# Gateway.net
KiCad netlist of a schematic drawn in Altium Designer
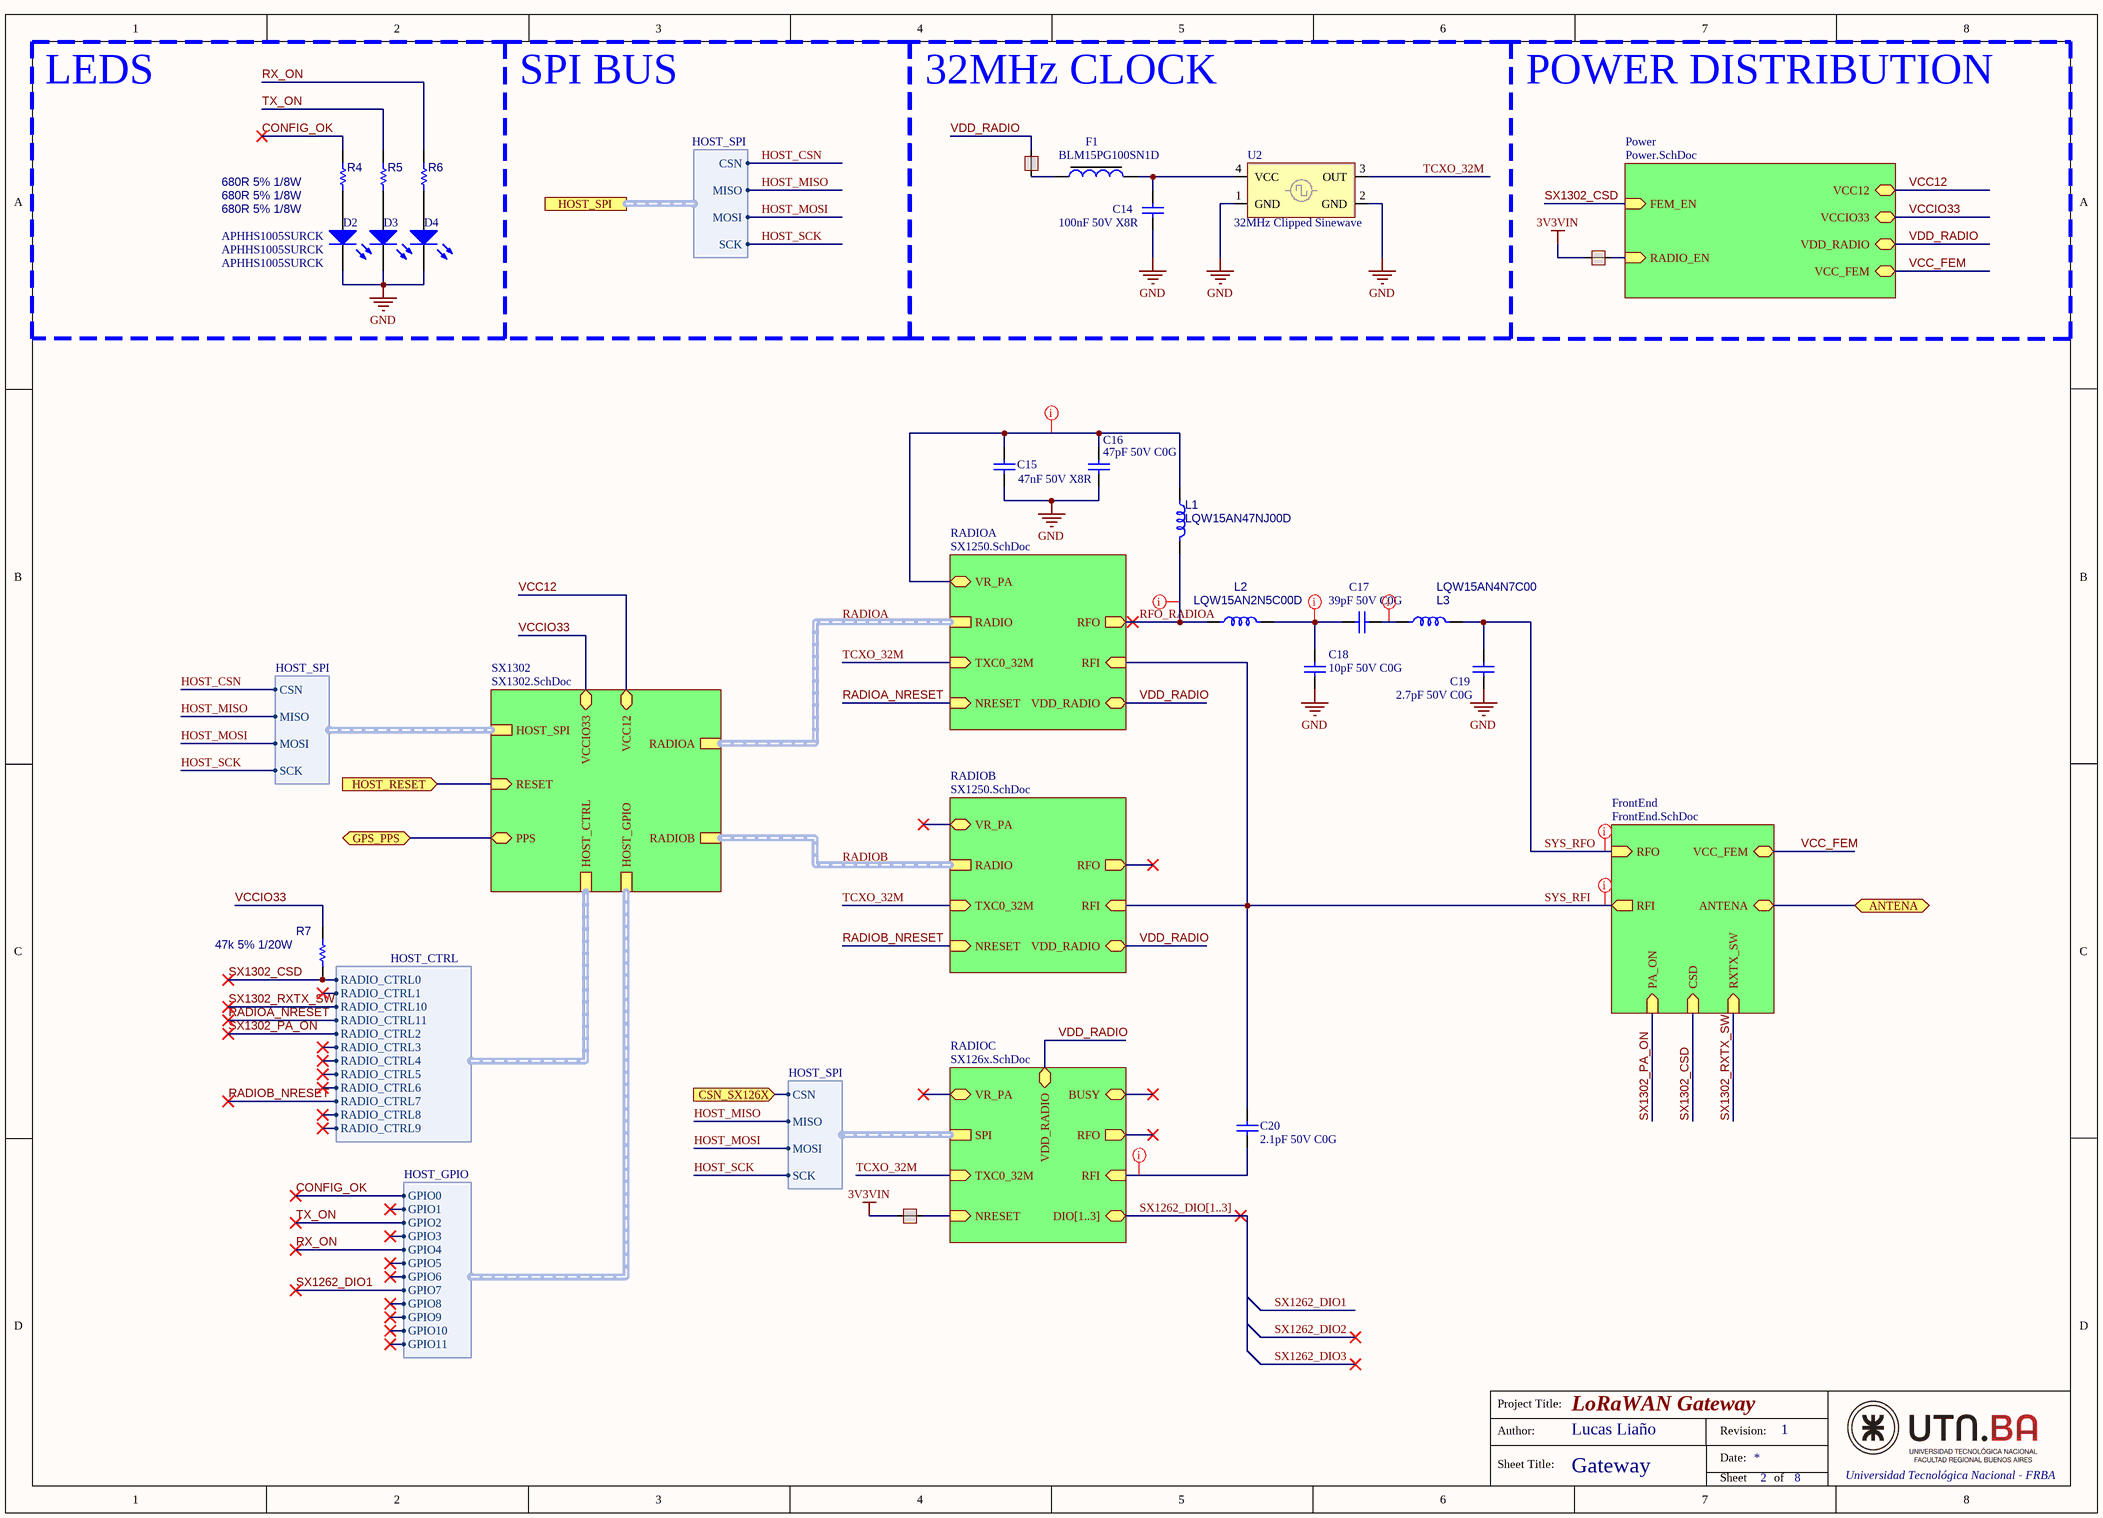
[diagram p0: Gateway.SchDoc]

(export (version "E")
  (design (tool "Eeschema 10.0.6"))
  (components
    (comp (ref "C14")
      (value "100nF 50V X8R")
      (footprint "C_0603")
      (description "Capacitor")
      (fields (field (name "MPN") "GCM188R91H102KA37D") (field (name "MANUFACTURER") "Murata Electronics"))
      (libsource (lib "lorawan_gateway") (part "Cap"))
    )
    (comp (ref "C15")
      (value "47nF 50V X8R")
      (footprint "C_0603")
      (description "Capacitor")
      (fields (field (name "MPN") "GCM188R91H472KA37D") (field (name "MANUFACTURER") "Murata Electronics"))
      (libsource (lib "lorawan_gateway") (part "Cap"))
    )
    (comp (ref "C16")
      (value "47pF 50V C0G")
      (footprint "C_0603")
      (description "Capacitor")
      (fields (field (name "MPN") "0603J0500470GAT") (field (name "MANUFACTURER") "Knowless Syfer"))
      (libsource (lib "lorawan_gateway") (part "Cap"))
    )
    (comp (ref "C17")
      (value "39pF 50V C0G")
      (footprint "C_0603")
      (description "Capacitor")
      (fields (field (name "MPN") "06035A390FAT2A") (field (name "MANUFACTURER") "Kyocera AVX"))
      (libsource (lib "lorawan_gateway") (part "Cap"))
    )
    (comp (ref "C18")
      (value "10pF 50V C0G")
      (footprint "C_0603")
      (description "Capacitor")
      (fields (field (name "MPN") "GRM0335C1H100FA01D") (field (name "MANUFACTURER") "Murata Electronics"))
      (libsource (lib "lorawan_gateway") (part "Cap"))
    )
    (comp (ref "C19")
      (value "2.7pF 50V C0G")
      (footprint "C_0603")
      (description "Capacitor")
      (fields (field (name "MPN") "GRM0335C1H2R7WA01D") (field (name "MANUFACTURER") "Murata Electronics"))
      (libsource (lib "lorawan_gateway") (part "Cap"))
    )
    (comp (ref "C20")
      (value "2.1pF 50V C0G")
      (footprint "C_0603")
      (description "Capacitor")
      (fields (field (name "MPN") "ML03512R1BAT2A") (field (name "MANUFACTURER") "Kyocera AVX"))
      (libsource (lib "lorawan_gateway") (part "Cap"))
    )
    (comp (ref "D2")
      (value "APHHS1005SURCK")
      (footprint "D_0402")
      (description "LED")
      (fields (field (name "MANUFACTURER") "kingbright"))
      (libsource (lib "lorawan_gateway") (part "LED"))
    )
    (comp (ref "D3")
      (value "APHHS1005SURCK")
      (footprint "D_0402")
      (description "LED")
      (fields (field (name "MANUFACTURER") "kingbright"))
      (libsource (lib "lorawan_gateway") (part "LED"))
    )
    (comp (ref "D4")
      (value "APHHS1005SURCK")
      (footprint "D_0402")
      (description "LED")
      (fields (field (name "MANUFACTURER") "kingbright"))
      (libsource (lib "lorawan_gateway") (part "LED"))
    )
    (comp (ref "F1")
      (value "BLM15PG100SN1D")
      (footprint "L_0402")
      (description "Ferrite bead 10 ohm 1A")
      (fields (field (name "MANUFACTURER") "Murata Electronics"))
      (libsource (lib "lorawan_gateway") (part "Ferrite beads"))
    )
    (comp (ref "L1")
      (value "LQW15AN47NJ00D")
      (footprint "L_0402")
      (description "Inductor")
      (libsource (lib "lorawan_gateway") (part "IND"))
    )
    (comp (ref "L2")
      (value "LQW15AN2N5C00D")
      (footprint "L_0402")
      (description "Inductor")
      (libsource (lib "lorawan_gateway") (part "IND"))
    )
    (comp (ref "L3")
      (value "LQW15AN4N7C00")
      (footprint "L_0402")
      (description "Inductor")
      (libsource (lib "lorawan_gateway") (part "IND"))
    )
    (comp (ref "NT1")
      (value "NT")
      (footprint "NTIE12")
      (description "NET_TIE")
      (libsource (lib "lorawan_gateway") (part "NTIE"))
    )
    (comp (ref "NT13")
      (value "NT")
      (footprint "NTIE12")
      (description "NET_TIE")
      (libsource (lib "") (part "NTIE_1"))
    )
    (comp (ref "NT15")
      (value "NT")
      (footprint "NTIE12")
      (description "NET_TIE")
      (libsource (lib "lorawan_gateway") (part "NTIE"))
    )
    (comp (ref "R4")
      (value "680R 5% 1/8W")
      (footprint "0603[1608]")
      (description "Resistor")
      (fields
        (field (name "MANUFACTURER") "Panasonic Electronic Components")
        (field (name "MPN") "ERJ-H3GJ681V")
      )
      (libsource (lib "lorawan_gateway") (part "Res"))
    )
    (comp (ref "R5")
      (value "680R 5% 1/8W")
      (footprint "0603[1608]")
      (description "Resistor")
      (fields
        (field (name "MANUFACTURER") "Panasonic Electronic Components")
        (field (name "MPN") "ERJ-H3GJ681V")
      )
      (libsource (lib "lorawan_gateway") (part "Res"))
    )
    (comp (ref "R6")
      (value "680R 5% 1/8W")
      (footprint "0603[1608]")
      (description "Resistor")
      (fields
        (field (name "MANUFACTURER") "Panasonic Electronic Components")
        (field (name "MPN") "ERJ-H3GJ681V")
      )
      (libsource (lib "lorawan_gateway") (part "Res"))
    )
    (comp (ref "R7")
      (value "47k 5% 1/20W")
      (footprint "0603[1608]")
      (description "Resistor")
      (fields (field (name "MANUFACTURER") "Vishay") (field (name "MPN") "M55342K11B47K0MT1V"))
      (libsource (lib "lorawan_gateway") (part "Res"))
    )
    (comp (ref "U2")
      (value "32MHz Clipped Sinewave")
      (footprint "TCXO 2.0x1.6mm")
      (description "32MHz TCXO - Clipped Sinewave Output")
      (fields (field (name "MANUFACTURER") "NDK America") (field (name "MPN") "NT2016SA 32MHz END4263A"))
      (libsource (lib "lorawan_gateway") (part "TCXO"))
    )
  )
  (nets
    (net (code "8") (name "/CONFIG_OK") (class "Default")
      (node (ref "R4") (pin "2") (pinfunction "2_2") (pintype "passive+no_connect"))
    )
    (net (code "16") (name "/NRESET") (class "Default")
      (node (ref "NT1") (pin "2") (pinfunction "2_2") (pintype "passive"))
    )
    (net (code "19") (name "/RADIO_EN") (class "Default")
      (node (ref "NT15") (pin "2") (pinfunction "2_2") (pintype "passive"))
    )
    (net (code "20") (name "/RFI") (class "Default")
      (node (ref "C20") (pin "1") (pinfunction "1_1") (pintype "passive"))
    )
    (net (code "23") (name "/RFO_RADIOA") (class "Default")
      (node (ref "L1") (pin "2") (pinfunction "2_2") (pintype "passive"))
      (node (ref "L2") (pin "1") (pinfunction "1_1") (pintype "passive"))
    )
    (net (code "24") (name "/RX_ON") (class "Default")
      (node (ref "R6") (pin "2") (pinfunction "2_2") (pintype "passive"))
    )
    (net (code "29") (name "/SX1302_CSD") (class "Default")
      (node (ref "R7") (pin "1") (pinfunction "1_1") (pintype "passive+no_connect"))
    )
    (net (code "32") (name "/SYS_RFI") (class "Default")
      (node (ref "C20") (pin "2") (pinfunction "2_2") (pintype "passive"))
    )
    (net (code "33") (name "/SYS_RFO") (class "Default")
      (node (ref "C19") (pin "1") (pinfunction "1_1") (pintype "passive"))
      (node (ref "L3") (pin "2") (pinfunction "2_2") (pintype "passive"))
    )
    (net (code "34") (name "/TCXO_32M") (class "Default")
      (node (ref "U2") (pin "3") (pinfunction "OUT_3") (pintype "passive"))
    )
    (net (code "35") (name "/TX_ON") (class "Default")
      (node (ref "R5") (pin "2") (pinfunction "2_2") (pintype "passive"))
    )
    (net (code "37") (name "/VCCIO33") (class "Default")
      (node (ref "R7") (pin "2") (pinfunction "2_2") (pintype "passive"))
    )
    (net (code "39") (name "/VDD_RADIO") (class "Default")
      (node (ref "NT13") (pin "2") (pinfunction "2_2") (pintype "passive"))
    )
    (net (code "42") (name "/VR_PA_2") (class "Default")
      (node (ref "C15") (pin "1") (pinfunction "1_1") (pintype "passive"))
      (node (ref "C16") (pin "1") (pinfunction "1_1") (pintype "passive"))
      (node (ref "L1") (pin "1") (pinfunction "1_1") (pintype "passive"))
    )
    (net (code "48") (name "3V3VIN") (class "Default")
      (node (ref "NT1") (pin "1") (pinfunction "1_1") (pintype "passive"))
      (node (ref "NT15") (pin "1") (pinfunction "1_1") (pintype "passive"))
    )
    (net (code "49") (name "GND") (class "Default")
      (node (ref "C14") (pin "2") (pinfunction "2_2") (pintype "passive"))
      (node (ref "C15") (pin "2") (pinfunction "2_2") (pintype "passive"))
      (node (ref "C16") (pin "2") (pinfunction "2_2") (pintype "passive"))
      (node (ref "C18") (pin "1") (pinfunction "1_1") (pintype "passive"))
      (node (ref "C19") (pin "2") (pinfunction "2_2") (pintype "passive"))
      (node (ref "D2") (pin "2") (pinfunction "K_2") (pintype "passive"))
      (node (ref "D3") (pin "2") (pinfunction "K_2") (pintype "passive"))
      (node (ref "D4") (pin "2") (pinfunction "K_2") (pintype "passive"))
      (node (ref "U2") (pin "1") (pinfunction "GND_1") (pintype "passive"))
      (node (ref "U2") (pin "2") (pinfunction "GND_2") (pintype "passive"))
    )
    (net (code "50") (name "Net-(C17-Pad1)") (class "Default")
      (node (ref "C17") (pin "1") (pinfunction "1_1") (pintype "passive"))
      (node (ref "C18") (pin "2") (pinfunction "2_2") (pintype "passive"))
      (node (ref "L2") (pin "2") (pinfunction "2_2") (pintype "passive"))
    )
    (net (code "51") (name "Net-(C17-Pad2)") (class "Default")
      (node (ref "C17") (pin "2") (pinfunction "2_2") (pintype "passive"))
      (node (ref "L3") (pin "1") (pinfunction "1_1") (pintype "passive"))
    )
    (net (code "52") (name "Net-(D2-A)") (class "Default")
      (node (ref "D2") (pin "1") (pinfunction "A_1") (pintype "passive"))
      (node (ref "R4") (pin "1") (pinfunction "1_1") (pintype "passive"))
    )
    (net (code "53") (name "Net-(D3-A)") (class "Default")
      (node (ref "D3") (pin "1") (pinfunction "A_1") (pintype "passive"))
      (node (ref "R5") (pin "1") (pinfunction "1_1") (pintype "passive"))
    )
    (net (code "54") (name "Net-(D4-A)") (class "Default")
      (node (ref "D4") (pin "1") (pinfunction "A_1") (pintype "passive"))
      (node (ref "R6") (pin "1") (pinfunction "1_1") (pintype "passive"))
    )
    (net (code "55") (name "Net-(F1-Pad1)") (class "Default")
      (node (ref "F1") (pin "1") (pinfunction "1_1") (pintype "passive"))
      (node (ref "NT13") (pin "1") (pinfunction "1_1") (pintype "passive"))
    )
    (net (code "56") (name "Net-(U2-VCC)") (class "Default")
      (node (ref "C14") (pin "1") (pinfunction "1_1") (pintype "passive"))
      (node (ref "F1") (pin "2") (pinfunction "2_2") (pintype "passive"))
      (node (ref "U2") (pin "4") (pinfunction "VCC_4") (pintype "passive"))
    )
  )
)
